# S7_IO.net
KiCad netlist of a schematic drawn in Altium Designer
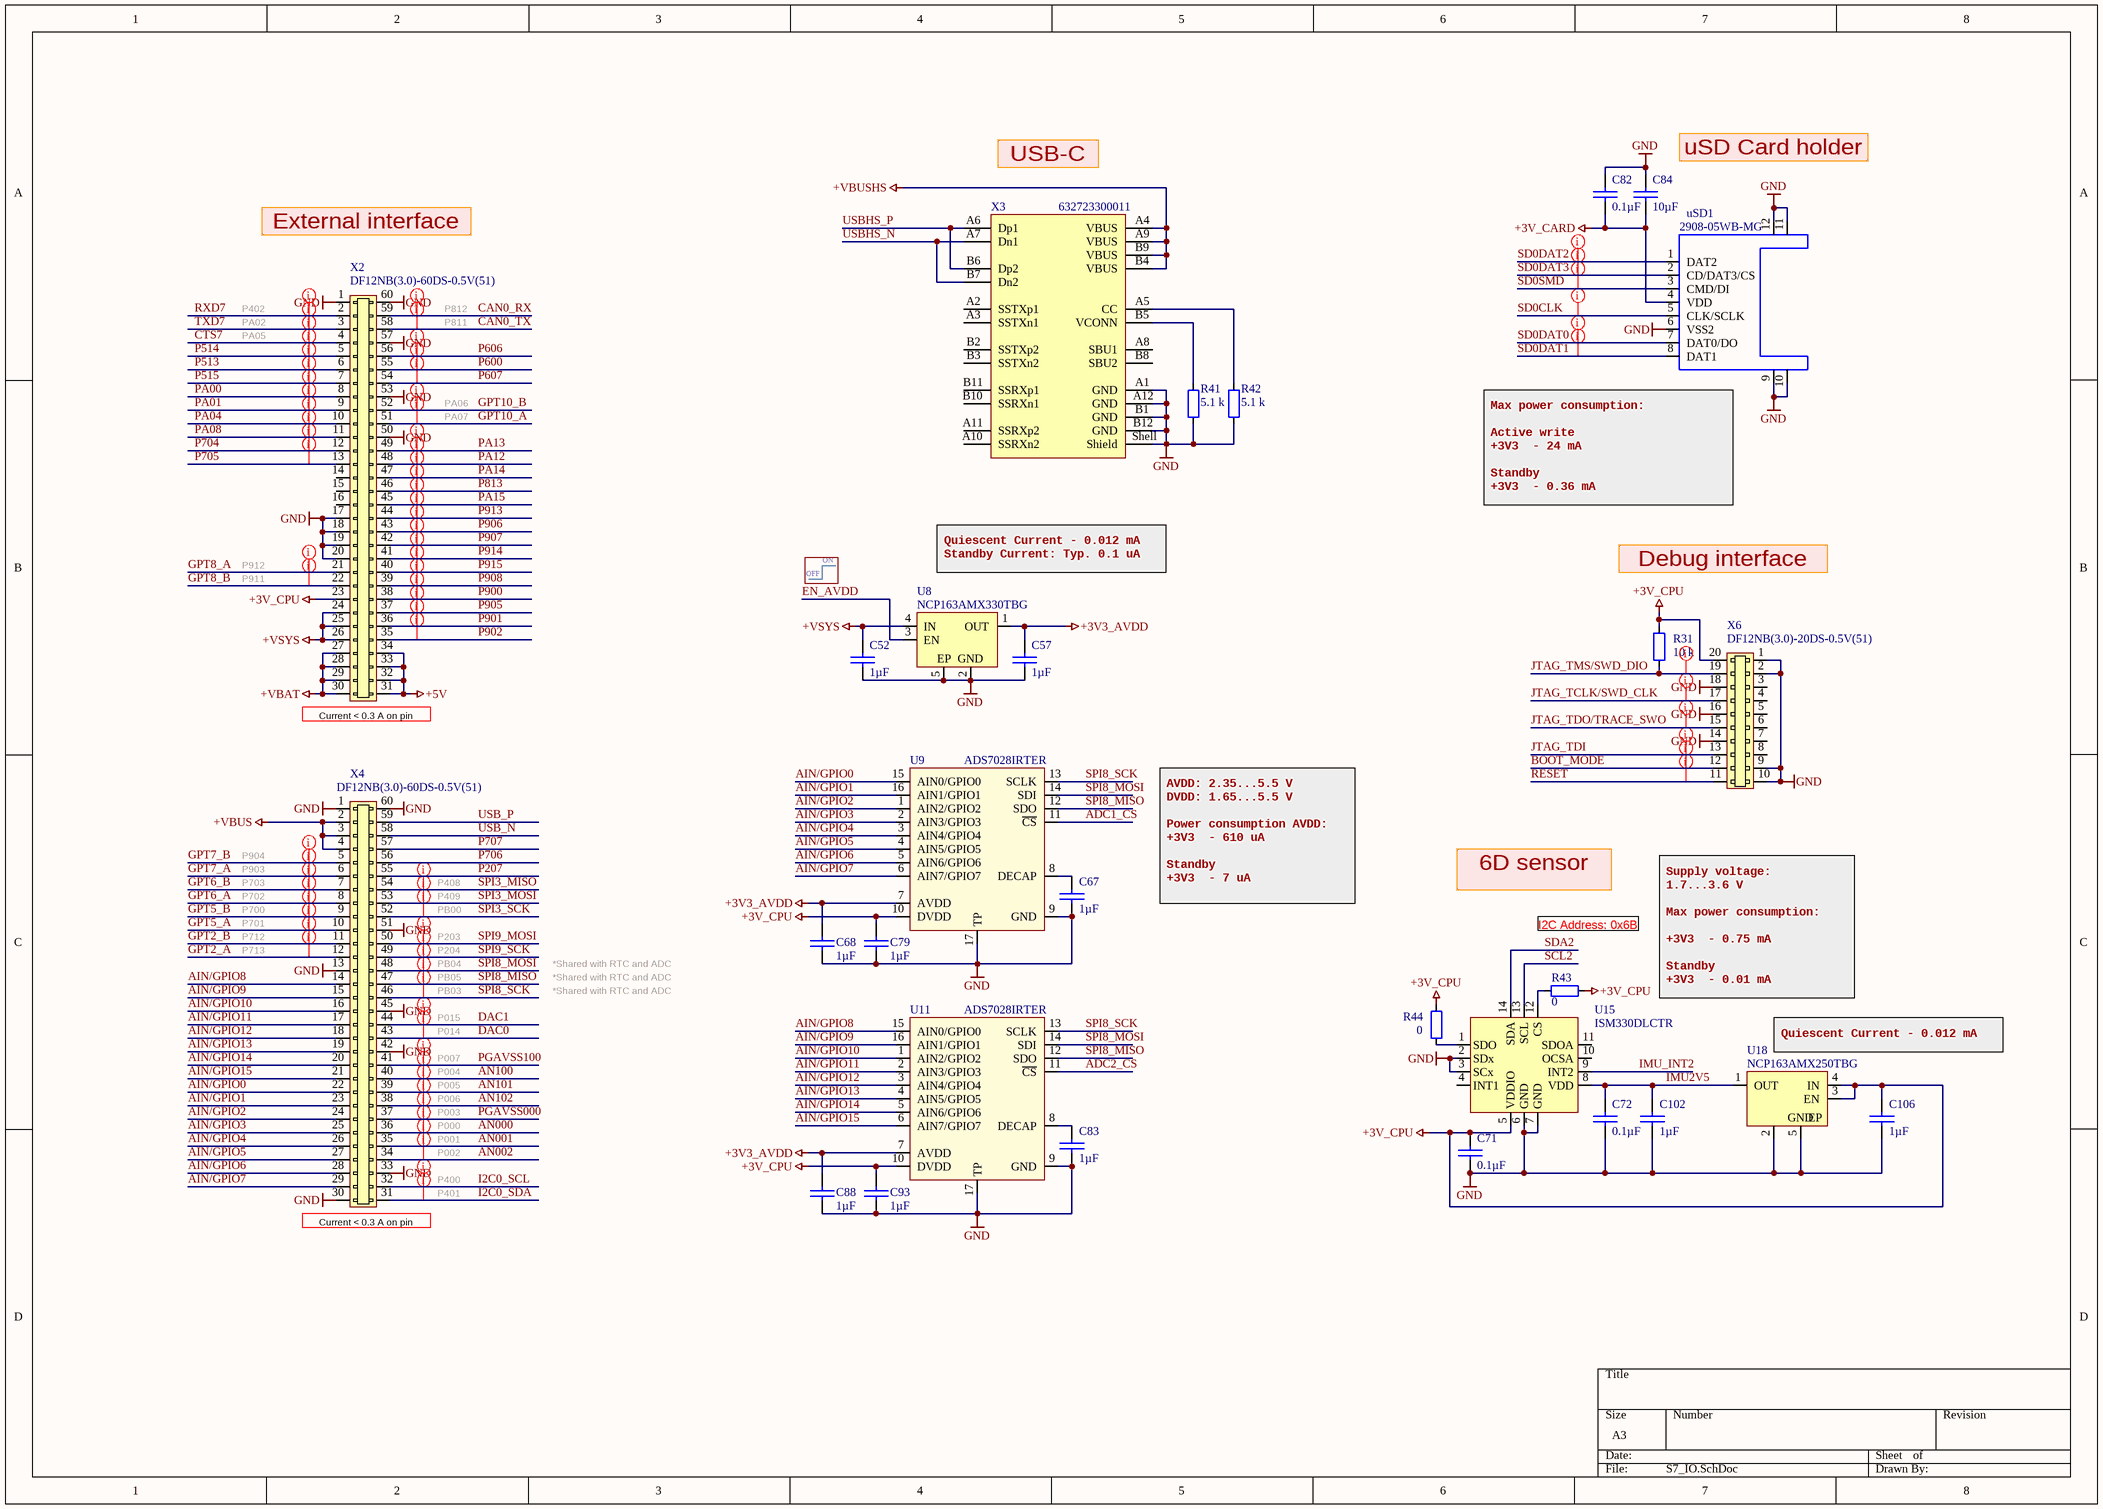
[diagram p0: S7_IO.SchDoc]

(export (version "E")
  (design (tool "Eeschema 10.0.6"))
  (components
    (comp (ref "C52")
      (value "1µF")
      (footprint "0402 CAP")
      (description "1µF, ±20%, 25V, X5R, 0402 (1005 Metric), -55°C ~ 85°C, -, General Purpose")
      (fields (field (name "PART NUMBER") "TMK105BJ105MV-F") (field (name "MANUFACTURER") "Taiyo Yuden"))
      (libsource (lib "ea_PassivComps") (part "Capacitor"))
    )
    (comp (ref "C57")
      (value "1µF")
      (footprint "0402 CAP")
      (description "1µF, ±20%, 25V, X5R, 0402 (1005 Metric), -55°C ~ 85°C, -, General Purpose")
      (fields (field (name "PART NUMBER") "TMK105BJ105MV-F") (field (name "MANUFACTURER") "Taiyo Yuden"))
      (libsource (lib "ea_PassivComps") (part "Capacitor"))
    )
    (comp (ref "C67")
      (value "1µF")
      (footprint "0402 CAP")
      (description "1µF, ±20%, 25V, X5R, 0402 (1005 Metric), -55°C ~ 85°C, -, General Purpose")
      (fields (field (name "PART NUMBER") "TMK105BJ105MV-F") (field (name "MANUFACTURER") "Taiyo Yuden"))
      (libsource (lib "ea_PassivComps") (part "Capacitor"))
    )
    (comp (ref "C68")
      (value "1µF")
      (footprint "0402 CAP")
      (description "1µF, ±20%, 25V, X5R, 0402 (1005 Metric), -55°C ~ 85°C, -, General Purpose")
      (fields (field (name "PART NUMBER") "TMK105BJ105MV-F") (field (name "MANUFACTURER") "Taiyo Yuden"))
      (libsource (lib "ea_PassivComps") (part "Capacitor"))
    )
    (comp (ref "C71")
      (value "0.1µF")
      (footprint "0402 CAP")
      (description "0.1µF, ±10%, 50V, X7R, 0402 (1005 Metric), -55°C ~ 125°C, -, General Purpose")
      (fields
        (field (name "PART NUMBER") "0402B104K500CT")
        (field (name "MANUFACTURER") "Walsin Technology Corporation")
      )
      (libsource (lib "ea_PassivComps") (part "Capacitor"))
    )
    (comp (ref "C72")
      (value "0.1µF")
      (footprint "0402 CAP")
      (description "0.1µF, ±10%, 50V, X7R, 0402 (1005 Metric), -55°C ~ 125°C, -, General Purpose")
      (fields
        (field (name "PART NUMBER") "0402B104K500CT")
        (field (name "MANUFACTURER") "Walsin Technology Corporation")
      )
      (libsource (lib "ea_PassivComps") (part "Capacitor"))
    )
    (comp (ref "C79")
      (value "1µF")
      (footprint "0402 CAP")
      (description "1µF, ±20%, 25V, X5R, 0402 (1005 Metric), -55°C ~ 85°C, -, General Purpose")
      (fields (field (name "PART NUMBER") "TMK105BJ105MV-F") (field (name "MANUFACTURER") "Taiyo Yuden"))
      (libsource (lib "ea_PassivComps") (part "Capacitor"))
    )
    (comp (ref "C82")
      (value "0.1µF")
      (footprint "0402 CAP")
      (description "0.1µF, ±10%, 50V, X7R, 0402 (1005 Metric), -55°C ~ 125°C, -, General Purpose")
      (fields
        (field (name "PART NUMBER") "0402B104K500CT")
        (field (name "MANUFACTURER") "Walsin Technology Corporation")
      )
      (libsource (lib "ea_PassivComps") (part "Capacitor"))
    )
    (comp (ref "C83")
      (value "1µF")
      (footprint "0402 CAP")
      (description "1µF, ±20%, 25V, X5R, 0402 (1005 Metric), -55°C ~ 85°C, -, General Purpose")
      (fields (field (name "PART NUMBER") "TMK105BJ105MV-F") (field (name "MANUFACTURER") "Taiyo Yuden"))
      (libsource (lib "ea_PassivComps") (part "Capacitor"))
    )
    (comp (ref "C84")
      (value "10µF")
      (footprint "0603 CAP")
      (description "10µF, ±10%, 16V, X5R, 0603 (1608 Metric), -55°C ~ 85°C, -, Automotive")
      (fields
        (field (name "PART NUMBER") "GRT188R61C106KE13D")
        (field (name "MANUFACTURER") "Murata Electronics North America")
      )
      (libsource (lib "ea_PassivComps") (part "Capacitor"))
    )
    (comp (ref "C88")
      (value "1µF")
      (footprint "0402 CAP")
      (description "1µF, ±20%, 25V, X5R, 0402 (1005 Metric), -55°C ~ 85°C, -, General Purpose")
      (fields (field (name "PART NUMBER") "TMK105BJ105MV-F") (field (name "MANUFACTURER") "Taiyo Yuden"))
      (libsource (lib "ea_PassivComps") (part "Capacitor"))
    )
    (comp (ref "C93")
      (value "1µF")
      (footprint "0402 CAP")
      (description "1µF, ±20%, 25V, X5R, 0402 (1005 Metric), -55°C ~ 85°C, -, General Purpose")
      (fields (field (name "PART NUMBER") "TMK105BJ105MV-F") (field (name "MANUFACTURER") "Taiyo Yuden"))
      (libsource (lib "ea_PassivComps") (part "Capacitor"))
    )
    (comp (ref "C102")
      (value "1µF")
      (footprint "0402 CAP")
      (description "1µF, ±20%, 25V, X5R, 0402 (1005 Metric), -55°C ~ 85°C, -, General Purpose")
      (fields (field (name "PART NUMBER") "TMK105BJ105MV-F") (field (name "MANUFACTURER") "Taiyo Yuden"))
      (libsource (lib "ea_PassivComps") (part "Capacitor"))
    )
    (comp (ref "C106")
      (value "1µF")
      (footprint "0402 CAP")
      (description "1µF, ±20%, 25V, X5R, 0402 (1005 Metric), -55°C ~ 85°C, -, General Purpose")
      (fields (field (name "PART NUMBER") "TMK105BJ105MV-F") (field (name "MANUFACTURER") "Taiyo Yuden"))
      (libsource (lib "ea_PassivComps") (part "Capacitor"))
    )
    (comp (ref "R31")
      (value "10 k")
      (footprint "0402")
      (fields
        (field (name "MANUFACTURER") "Stackpole Electronics Inc")
        (field (name "TOLERANCE") "±1%")
        (field (name "PARTNUM") "RMCF0402FT10K0CT-ND")
      )
      (libsource (lib "ea_PassivComps") (part "Resistor"))
    )
    (comp (ref "R41")
      (value "5.1 k")
      (footprint "0402")
      (fields
        (field (name "MANUFACTURER") "Stackpole Electronics Inc")
        (field (name "TOLERANCE") "±1%")
        (field (name "VOLTAGE") "75V")
      )
      (libsource (lib "ea_PassivComps") (part "Resistor"))
    )
    (comp (ref "R42")
      (value "5.1 k")
      (footprint "0402")
      (fields
        (field (name "MANUFACTURER") "Stackpole Electronics Inc")
        (field (name "TOLERANCE") "±1%")
        (field (name "VOLTAGE") "75V")
      )
      (libsource (lib "ea_PassivComps") (part "Resistor"))
    )
    (comp (ref "R43")
      (value "0")
      (footprint "0402")
      (description "0 Ohms Jumper 0.063W, 1/16W Chip Resistor 0402 (1005 Metric) Thick Film")
      (fields (field (name "MANUFACTURER") "Walsin Technology Corporation") (field (name "VOLTAGE") "50 V"))
      (libsource (lib "") (part "WR04X000 PTL_1"))
    )
    (comp (ref "R44")
      (value "0")
      (footprint "0402")
      (description "0 Ohms Jumper 0.063W, 1/16W Chip Resistor 0402 (1005 Metric) Thick Film")
      (fields (field (name "MANUFACTURER") "Walsin Technology Corporation") (field (name "VOLTAGE") "50 V"))
      (libsource (lib "ea_Resistors_0402") (part "WR04X000 PTL"))
    )
    (comp (ref "U8")
      (value "NCP163AMX330TBG")
      (footprint "4-XDFN")
      (description "LDO 3.3V, 250 mA, Vin < 5.5V, Iq < 20uA, -40..+125 C,  4-XDFN (1x1)")
      (fields
        (field (name "MANUFACTURER") "ON Semiconductor")
        (field (name "PARTNUM") "NCP163AMX330TBGOSCT-ND")
      )
      (libsource (lib "ea_IC_Linear_reg_LDO") (part "NCP163AMX330TBG"))
    )
    (comp (ref "U9")
      (value "ADS7028IRTER")
      (footprint "WQFN-16 3x3mm TI")
      (description "12 Bit Analog to Digital Converter 8 Input 1 SAR, 2.35V ~ 5.5V, 16-WQFN (3x3),  -40°C ~ 85°C")
      (fields
        (field (name "MANUFACTURER") "Texas Instruments")
        (field (name "PARTNUM") "296-ADS7028IRTERCT-ND")
      )
      (libsource (lib "ea_IC_ADC") (part "ADS7028IRTER"))
    )
    (comp (ref "U11")
      (value "ADS7028IRTER")
      (footprint "WQFN-16 3x3mm TI")
      (description "12 Bit Analog to Digital Converter 8 Input 1 SAR, 2.35V ~ 5.5V, 16-WQFN (3x3),  -40°C ~ 85°C")
      (fields
        (field (name "MANUFACTURER") "Texas Instruments")
        (field (name "PARTNUM") "296-ADS7028IRTERCT-ND")
      )
      (libsource (lib "ea_IC_ADC") (part "ADS7028IRTER"))
    )
    (comp (ref "U15")
      (value "ISM330DLCTR")
      (footprint "LGA-14 BOSCH")
      (description "Accelerometer, Gyroscope, Temperature, 3 Axis Sensor I²C, SPI , -40°C ~ 85°C, 14-LGA (2.5x3)")
      (fields (field (name "MANUFACTURER") "STMicroelectronics") (field (name "PARTNUM") "497-17583-1-ND"))
      (libsource (lib "ea_IC_sensors") (part "ISM330DLCTR"))
    )
    (comp (ref "U18")
      (value "NCP163AMX250TBG")
      (footprint "4-XDFN")
      (description "LDO 2.5V, 250 mA, Vin < 5.5V, Iq < 20uA, -40..+125 C,  4-XDFN (1x1)")
      (fields
        (field (name "MANUFACTURER") "ON Semiconductor")
        (field (name "PARTNUM") "NCP163AMX250TBGOSCT-ND")
      )
      (libsource (lib "ea_IC_Power_Reg_Ref_Sw") (part "NCP163AMX250TBG"))
    )
    (comp (ref "uSD1")
      (value "2908-05WB-MG")
      (footprint "2908-05WB-MG")
      (description "microSD cadr holder")
      (fields (field (name "MANUFACTURER") "3M"))
      (libsource (lib "ea_CARD_holders") (part "2908-05WB-MG"))
    )
    (comp (ref "X2")
      (value "DF12NB(3.0)-60DS-0.5V(51)")
      (footprint "DF12NB(3.0)-60DS-0.5V(51)")
      (fields
        (field (name "MANUFACTURER") "Hirose Electric")
        (field (name "PARTNUM") "26-DF12NB(3.0)-60DS-0.5V(51)CT-ND")
      )
      (libsource (lib "ea_Connectors_0.5_mm_pitch") (part "DF12NB(3.0)-60DS-0.5V(51)"))
    )
    (comp (ref "X3")
      (value "632723300011")
      (footprint "632723300011")
      (description "WR-USB 3.1 Type C, Receptacle, Horizontal, THR")
      (fields (field (name "MANUFACTURER") "Wurth Elektronik"))
      (libsource (lib "WR-USB") (part "632723300011"))
    )
    (comp (ref "X4")
      (value "DF12NB(3.0)-60DS-0.5V(51)")
      (footprint "DF12NB(3.0)-60DS-0.5V(51)")
      (fields
        (field (name "MANUFACTURER") "Hirose Electric")
        (field (name "PARTNUM") "26-DF12NB(3.0)-60DS-0.5V(51)CT-ND")
      )
      (libsource (lib "ea_Connectors_0.5_mm_pitch") (part "DF12NB(3.0)-60DS-0.5V(51)"))
    )
    (comp (ref "X6")
      (value "DF12NB(3.0)-20DS-0.5V(51)")
      (footprint "DF12NB(3.0)-20DS-0.5V(51)")
      (fields
        (field (name "MANUFACTURER") "Hirose Electric")
        (field (name "PARTNUM") "26-DF12NB(3.0)-20DS-0.5V(51)CT-ND - Cut Tape (CT)")
      )
      (libsource (lib "ea_Connectors_0.5_mm_pitch") (part "DF12NB(3.0)-20DS-0.5V(51)"))
    )
  )
  (nets
    (net (code "1") (name "+3V3_AVDD") (class "Default")
      (node (ref "C57") (pin "1") (pinfunction "1_1") (pintype "passive"))
      (node (ref "C68") (pin "1") (pinfunction "1_1") (pintype "passive"))
      (node (ref "C88") (pin "1") (pinfunction "1_1") (pintype "passive"))
      (node (ref "U11") (pin "7") (pinfunction "AVDD_7") (pintype "passive"))
      (node (ref "U8") (pin "1") (pinfunction "OUT_1") (pintype "power_in"))
      (node (ref "U9") (pin "7") (pinfunction "AVDD_7") (pintype "passive"))
    )
    (net (code "2") (name "+3V_CARD") (class "Default")
      (node (ref "C82") (pin "2") (pinfunction "2_2") (pintype "passive"))
      (node (ref "C84") (pin "2") (pinfunction "2_2") (pintype "passive"))
      (node (ref "uSD1") (pin "4") (pinfunction "VDD_4") (pintype "passive"))
    )
    (net (code "3") (name "+3V_CPU") (class "Default")
      (node (ref "C106") (pin "1") (pinfunction "1_1") (pintype "passive"))
      (node (ref "C71") (pin "1") (pinfunction "1_1") (pintype "passive"))
      (node (ref "C79") (pin "1") (pinfunction "1_1") (pintype "passive"))
      (node (ref "C93") (pin "1") (pinfunction "1_1") (pintype "passive"))
      (node (ref "R31") (pin "2") (pinfunction "2_2") (pintype "passive"))
      (node (ref "R43") (pin "1") (pinfunction "1_1") (pintype "passive"))
      (node (ref "R44") (pin "2") (pinfunction "2_2") (pintype "passive"))
      (node (ref "U11") (pin "10") (pinfunction "DVDD_10") (pintype "passive"))
      (node (ref "U15") (pin "5") (pinfunction "VDDIO_5") (pintype "passive"))
      (node (ref "U18") (pin "3") (pinfunction "EN_3") (pintype "power_in"))
      (node (ref "U18") (pin "4") (pinfunction "IN_4") (pintype "power_in"))
      (node (ref "U9") (pin "10") (pinfunction "DVDD_10") (pintype "passive"))
      (node (ref "X2") (pin "23") (pinfunction "23_23") (pintype "passive"))
      (node (ref "X6") (pin "20") (pinfunction "11_20") (pintype "passive"))
    )
    (net (code "4") (name "+5V") (class "Default")
      (node (ref "X2") (pin "31") (pinfunction "31_31") (pintype "passive"))
      (node (ref "X2") (pin "32") (pinfunction "32_32") (pintype "passive"))
      (node (ref "X2") (pin "33") (pinfunction "33_33") (pintype "passive"))
      (node (ref "X2") (pin "34") (pinfunction "34_34") (pintype "passive"))
    )
    (net (code "5") (name "+VBAT") (class "Default")
      (node (ref "X2") (pin "27") (pinfunction "27_27") (pintype "passive"))
      (node (ref "X2") (pin "28") (pinfunction "28_28") (pintype "passive"))
      (node (ref "X2") (pin "29") (pinfunction "29_29") (pintype "passive"))
      (node (ref "X2") (pin "30") (pinfunction "30_30") (pintype "passive"))
    )
    (net (code "6") (name "+VBUS") (class "Default")
      (node (ref "X4") (pin "2") (pinfunction "2_2") (pintype "passive"))
      (node (ref "X4") (pin "3") (pinfunction "3_3") (pintype "passive"))
      (node (ref "X4") (pin "4") (pinfunction "4_4") (pintype "passive"))
    )
    (net (code "7") (name "+VBUSHS") (class "Default")
      (node (ref "X3") (pin "A4") (pinfunction "VBUS_A4") (pintype "passive"))
      (node (ref "X3") (pin "A9") (pinfunction "VBUS_A9") (pintype "passive"))
      (node (ref "X3") (pin "B4") (pinfunction "VBUS_B4") (pintype "passive"))
      (node (ref "X3") (pin "B9") (pinfunction "VBUS_B9") (pintype "passive"))
    )
    (net (code "8") (name "+VSYS") (class "Default")
      (node (ref "C52") (pin "1") (pinfunction "1_1") (pintype "passive"))
      (node (ref "U8") (pin "4") (pinfunction "IN_4") (pintype "power_in"))
      (node (ref "X2") (pin "24") (pinfunction "24_24") (pintype "passive"))
      (node (ref "X2") (pin "25") (pinfunction "25_25") (pintype "passive"))
      (node (ref "X2") (pin "26") (pinfunction "26_26") (pintype "passive"))
    )
    (net (code "9") (name "/ADC1_CS") (class "Default")
      (node (ref "U9") (pin "11") (pinfunction "~{CS}_11") (pintype "passive"))
    )
    (net (code "10") (name "/ADC2_CS") (class "Default")
      (node (ref "U11") (pin "11") (pinfunction "~{CS}_11") (pintype "passive"))
    )
    (net (code "11") (name "/AIN{slash}GPIO0") (class "Default")
      (node (ref "U9") (pin "15") (pinfunction "AIN0/GPIO0_15") (pintype "passive"))
      (node (ref "X4") (pin "22") (pinfunction "22_22") (pintype "passive"))
    )
    (net (code "12") (name "/AIN{slash}GPIO1") (class "Default")
      (node (ref "U9") (pin "16") (pinfunction "AIN1/GPIO1_16") (pintype "passive"))
      (node (ref "X4") (pin "23") (pinfunction "23_23") (pintype "passive"))
    )
    (net (code "13") (name "/AIN{slash}GPIO2") (class "Default")
      (node (ref "U9") (pin "1") (pinfunction "AIN2/GPIO2_1") (pintype "passive"))
      (node (ref "X4") (pin "24") (pinfunction "24_24") (pintype "passive"))
    )
    (net (code "14") (name "/AIN{slash}GPIO3") (class "Default")
      (node (ref "U9") (pin "2") (pinfunction "AIN3/GPIO3_2") (pintype "passive"))
      (node (ref "X4") (pin "25") (pinfunction "25_25") (pintype "passive"))
    )
    (net (code "15") (name "/AIN{slash}GPIO4") (class "Default")
      (node (ref "U9") (pin "3") (pinfunction "AIN4/GPIO4_3") (pintype "passive"))
      (node (ref "X4") (pin "26") (pinfunction "26_26") (pintype "passive"))
    )
    (net (code "16") (name "/AIN{slash}GPIO5") (class "Default")
      (node (ref "U9") (pin "4") (pinfunction "AIN5/GPIO5_4") (pintype "passive"))
      (node (ref "X4") (pin "27") (pinfunction "27_27") (pintype "passive"))
    )
    (net (code "17") (name "/AIN{slash}GPIO6") (class "Default")
      (node (ref "U9") (pin "5") (pinfunction "AIN6/GPIO6_5") (pintype "passive"))
      (node (ref "X4") (pin "28") (pinfunction "28_28") (pintype "passive"))
    )
    (net (code "18") (name "/AIN{slash}GPIO7") (class "Default")
      (node (ref "U9") (pin "6") (pinfunction "AIN7/GPIO7_6") (pintype "passive"))
      (node (ref "X4") (pin "29") (pinfunction "29_29") (pintype "passive"))
    )
    (net (code "19") (name "/AIN{slash}GPIO8") (class "Default")
      (node (ref "U11") (pin "15") (pinfunction "AIN0/GPIO0_15") (pintype "passive"))
      (node (ref "X4") (pin "14") (pinfunction "14_14") (pintype "passive"))
    )
    (net (code "20") (name "/AIN{slash}GPIO9") (class "Default")
      (node (ref "U11") (pin "16") (pinfunction "AIN1/GPIO1_16") (pintype "passive"))
      (node (ref "X4") (pin "15") (pinfunction "15_15") (pintype "passive"))
    )
    (net (code "21") (name "/AIN{slash}GPIO10") (class "Default")
      (node (ref "U11") (pin "1") (pinfunction "AIN2/GPIO2_1") (pintype "passive"))
      (node (ref "X4") (pin "16") (pinfunction "16_16") (pintype "passive"))
    )
    (net (code "22") (name "/AIN{slash}GPIO11") (class "Default")
      (node (ref "U11") (pin "2") (pinfunction "AIN3/GPIO3_2") (pintype "passive"))
      (node (ref "X4") (pin "17") (pinfunction "17_17") (pintype "passive"))
    )
    (net (code "23") (name "/AIN{slash}GPIO12") (class "Default")
      (node (ref "U11") (pin "3") (pinfunction "AIN4/GPIO4_3") (pintype "passive"))
      (node (ref "X4") (pin "18") (pinfunction "18_18") (pintype "passive"))
    )
    (net (code "24") (name "/AIN{slash}GPIO13") (class "Default")
      (node (ref "U11") (pin "4") (pinfunction "AIN5/GPIO5_4") (pintype "passive"))
      (node (ref "X4") (pin "19") (pinfunction "19_19") (pintype "passive"))
    )
    (net (code "25") (name "/AIN{slash}GPIO14") (class "Default")
      (node (ref "U11") (pin "5") (pinfunction "AIN6/GPIO6_5") (pintype "passive"))
      (node (ref "X4") (pin "20") (pinfunction "20_20") (pintype "passive"))
    )
    (net (code "26") (name "/AIN{slash}GPIO15") (class "Default")
      (node (ref "U11") (pin "6") (pinfunction "AIN7/GPIO7_6") (pintype "passive"))
      (node (ref "X4") (pin "21") (pinfunction "21_21") (pintype "passive"))
    )
    (net (code "27") (name "/AN000") (class "Default")
      (node (ref "X4") (pin "36") (pinfunction "36_36") (pintype "passive"))
    )
    (net (code "28") (name "/AN001") (class "Default")
      (node (ref "X4") (pin "35") (pinfunction "35_35") (pintype "passive"))
    )
    (net (code "29") (name "/AN002") (class "Default")
      (node (ref "X4") (pin "34") (pinfunction "34_34") (pintype "passive"))
    )
    (net (code "30") (name "/AN100") (class "Default")
      (node (ref "X4") (pin "40") (pinfunction "40_40") (pintype "passive"))
    )
    (net (code "31") (name "/AN101") (class "Default")
      (node (ref "X4") (pin "39") (pinfunction "39_39") (pintype "passive"))
    )
    (net (code "32") (name "/AN102") (class "Default")
      (node (ref "X4") (pin "38") (pinfunction "38_38") (pintype "passive"))
    )
    (net (code "33") (name "/BOOT_MODE") (class "Default")
      (node (ref "X6") (pin "12") (pinfunction "7_12") (pintype "passive"))
    )
    (net (code "34") (name "/CAN0_RX") (class "Default")
      (node (ref "X2") (pin "59") (pinfunction "59_59") (pintype "passive"))
    )
    (net (code "35") (name "/CAN0_TX") (class "Default")
      (node (ref "X2") (pin "58") (pinfunction "58_58") (pintype "passive"))
    )
    (net (code "36") (name "/CTS7") (class "Default")
      (node (ref "X2") (pin "4") (pinfunction "4_4") (pintype "passive"))
    )
    (net (code "37") (name "/DAC0") (class "Default")
      (node (ref "X4") (pin "43") (pinfunction "43_43") (pintype "passive"))
    )
    (net (code "38") (name "/DAC1") (class "Default")
      (node (ref "X4") (pin "44") (pinfunction "44_44") (pintype "passive"))
    )
    (net (code "39") (name "/EN_AVDD") (class "Default")
      (node (ref "U8") (pin "3") (pinfunction "EN_3") (pintype "power_in"))
    )
    (net (code "40") (name "/GPT2_A") (class "Default")
      (node (ref "X4") (pin "12") (pinfunction "12_12") (pintype "passive"))
    )
    (net (code "41") (name "/GPT2_B") (class "Default")
      (node (ref "X4") (pin "11") (pinfunction "11_11") (pintype "passive"))
    )
    (net (code "42") (name "/GPT5_A") (class "Default")
      (node (ref "X4") (pin "10") (pinfunction "10_10") (pintype "passive"))
    )
    (net (code "43") (name "/GPT5_B") (class "Default")
      (node (ref "X4") (pin "9") (pinfunction "9_9") (pintype "passive"))
    )
    (net (code "44") (name "/GPT6_A") (class "Default")
      (node (ref "X4") (pin "8") (pinfunction "8_8") (pintype "passive"))
    )
    (net (code "45") (name "/GPT6_B") (class "Default")
      (node (ref "X4") (pin "7") (pinfunction "7_7") (pintype "passive"))
    )
    (net (code "46") (name "/GPT7_A") (class "Default")
      (node (ref "X4") (pin "6") (pinfunction "6_6") (pintype "passive"))
    )
    (net (code "47") (name "/GPT7_B") (class "Default")
      (node (ref "X4") (pin "5") (pinfunction "5_5") (pintype "passive"))
    )
    (net (code "48") (name "/GPT8_A") (class "Default")
      (node (ref "X2") (pin "21") (pinfunction "21_21") (pintype "passive"))
    )
    (net (code "49") (name "/GPT8_B") (class "Default")
      (node (ref "X2") (pin "22") (pinfunction "22_22") (pintype "passive"))
    )
    (net (code "50") (name "/GPT10_A") (class "Default")
      (node (ref "X2") (pin "51") (pinfunction "51_51") (pintype "passive"))
    )
    (net (code "51") (name "/GPT10_B") (class "Default")
      (node (ref "X2") (pin "52") (pinfunction "52_52") (pintype "passive"))
    )
    (net (code "52") (name "/I2C0_SCL") (class "Default")
      (node (ref "X4") (pin "32") (pinfunction "32_32") (pintype "passive"))
    )
    (net (code "53") (name "/I2C0_SDA") (class "Default")
      (node (ref "X4") (pin "31") (pinfunction "31_31") (pintype "passive"))
    )
    (net (code "54") (name "/IMU2V5") (class "Default")
      (node (ref "C102") (pin "1") (pinfunction "1_1") (pintype "passive"))
      (node (ref "C72") (pin "1") (pinfunction "1_1") (pintype "passive"))
      (node (ref "U15") (pin "8") (pinfunction "VDD_8") (pintype "passive"))
      (node (ref "U18") (pin "1") (pinfunction "OUT_1") (pintype "power_in"))
    )
    (net (code "55") (name "/IMU_INT2") (class "Default")
      (node (ref "U15") (pin "9") (pinfunction "INT2_9") (pintype "passive"))
    )
    (net (code "56") (name "/JTAG_TCLK{slash}SWD_CLK") (class "Default")
      (node (ref "X6") (pin "17") (pinfunction "9_17") (pintype "passive"))
    )
    (net (code "57") (name "/JTAG_TDI") (class "Default")
      (node (ref "X6") (pin "13") (pinfunction "7_13") (pintype "passive"))
    )
    (net (code "58") (name "/JTAG_TDO{slash}TRACE_SWO") (class "Default")
      (node (ref "X6") (pin "15") (pinfunction "8_15") (pintype "passive"))
    )
    (net (code "59") (name "/JTAG_TMS{slash}SWD_DIO") (class "Default")
      (node (ref "R31") (pin "1") (pinfunction "1_1") (pintype "passive"))
      (node (ref "X6") (pin "19") (pinfunction "10_19") (pintype "passive"))
    )
    (net (code "60") (name "/P207") (class "Default")
      (node (ref "X4") (pin "55") (pinfunction "55_55") (pintype "passive"))
    )
    (net (code "61") (name "/P513") (class "Default")
      (node (ref "X2") (pin "6") (pinfunction "6_6") (pintype "passive"))
    )
    (net (code "62") (name "/P514") (class "Default")
      (node (ref "X2") (pin "5") (pinfunction "5_5") (pintype "passive"))
    )
    (net (code "63") (name "/P515") (class "Default")
      (node (ref "X2") (pin "7") (pinfunction "7_7") (pintype "passive"))
    )
    (net (code "64") (name "/P600") (class "Default")
      (node (ref "X2") (pin "55") (pinfunction "55_55") (pintype "passive"))
    )
    (net (code "65") (name "/P606") (class "Default")
      (node (ref "X2") (pin "56") (pinfunction "56_56") (pintype "passive"))
    )
    (net (code "66") (name "/P607") (class "Default")
      (node (ref "X2") (pin "54") (pinfunction "54_54") (pintype "passive"))
    )
    (net (code "67") (name "/P704") (class "Default")
      (node (ref "X2") (pin "12") (pinfunction "12_12") (pintype "passive"))
    )
    (net (code "68") (name "/P705") (class "Default")
      (node (ref "X2") (pin "13") (pinfunction "13_13") (pintype "passive"))
    )
    (net (code "69") (name "/P706") (class "Default")
      (node (ref "X4") (pin "56") (pinfunction "56_56") (pintype "passive"))
    )
    (net (code "70") (name "/P707") (class "Default")
      (node (ref "X4") (pin "57") (pinfunction "57_57") (pintype "passive"))
    )
    (net (code "71") (name "/P813") (class "Default")
      (node (ref "X2") (pin "46") (pinfunction "46_46") (pintype "passive"))
    )
    (net (code "72") (name "/P900") (class "Default")
      (node (ref "X2") (pin "38") (pinfunction "38_38") (pintype "passive"))
    )
    (net (code "73") (name "/P901") (class "Default")
      (node (ref "X2") (pin "36") (pinfunction "36_36") (pintype "passive"))
    )
    (net (code "74") (name "/P902") (class "Default")
      (node (ref "X2") (pin "35") (pinfunction "35_35") (pintype "passive"))
    )
    (net (code "75") (name "/P905") (class "Default")
      (node (ref "X2") (pin "37") (pinfunction "37_37") (pintype "passive"))
    )
    (net (code "76") (name "/P906") (class "Default")
      (node (ref "X2") (pin "43") (pinfunction "43_43") (pintype "passive"))
    )
    (net (code "77") (name "/P907") (class "Default")
      (node (ref "X2") (pin "42") (pinfunction "42_42") (pintype "passive"))
    )
    (net (code "78") (name "/P908") (class "Default")
      (node (ref "X2") (pin "39") (pinfunction "39_39") (pintype "passive"))
    )
    (net (code "79") (name "/P913") (class "Default")
      (node (ref "X2") (pin "44") (pinfunction "44_44") (pintype "passive"))
    )
    (net (code "80") (name "/P914") (class "Default")
      (node (ref "X2") (pin "41") (pinfunction "41_41") (pintype "passive"))
    )
    (net (code "81") (name "/P915") (class "Default")
      (node (ref "X2") (pin "40") (pinfunction "40_40") (pintype "passive"))
    )
    (net (code "82") (name "/PA00") (class "Default")
      (node (ref "X2") (pin "8") (pinfunction "8_8") (pintype "passive"))
    )
    (net (code "83") (name "/PA01") (class "Default")
      (node (ref "X2") (pin "9") (pinfunction "9_9") (pintype "passive"))
    )
    (net (code "84") (name "/PA04") (class "Default")
      (node (ref "X2") (pin "10") (pinfunction "10_10") (pintype "passive"))
    )
    (net (code "85") (name "/PA08") (class "Default")
      (node (ref "X2") (pin "11") (pinfunction "11_11") (pintype "passive"))
    )
    (net (code "86") (name "/PA12") (class "Default")
      (node (ref "X2") (pin "48") (pinfunction "48_48") (pintype "passive"))
    )
    (net (code "87") (name "/PA13") (class "Default")
      (node (ref "X2") (pin "49") (pinfunction "49_49") (pintype "passive"))
    )
    (net (code "88") (name "/PA14") (class "Default")
      (node (ref "X2") (pin "47") (pinfunction "47_47") (pintype "passive"))
    )
    (net (code "89") (name "/PA15") (class "Default")
      (node (ref "X2") (pin "45") (pinfunction "45_45") (pintype "passive"))
    )
    (net (code "90") (name "/PGAVSS000") (class "Default")
      (node (ref "X4") (pin "37") (pinfunction "37_37") (pintype "passive"))
    )
    (net (code "91") (name "/PGAVSS100") (class "Default")
      (node (ref "X4") (pin "41") (pinfunction "41_41") (pintype "passive"))
    )
    (net (code "92") (name "/RESET") (class "Default")
      (node (ref "X6") (pin "11") (pinfunction "6_11") (pintype "passive"))
    )
    (net (code "93") (name "/RXD7") (class "Default")
      (node (ref "X2") (pin "2") (pinfunction "2_2") (pintype "passive"))
    )
    (net (code "94") (name "/SCL2") (class "Default")
      (node (ref "U15") (pin "13") (pinfunction "SCL_13") (pintype "passive"))
    )
    (net (code "95") (name "/SD0CLK") (class "Default")
      (node (ref "uSD1") (pin "5") (pinfunction "CLK/SCLK_5") (pintype "passive"))
    )
    (net (code "96") (name "/SD0DAT0") (class "Default")
      (node (ref "uSD1") (pin "7") (pinfunction "DAT0/DO_7") (pintype "passive"))
    )
    (net (code "97") (name "/SD0DAT1") (class "Default")
      (node (ref "uSD1") (pin "8") (pinfunction "DAT1_8") (pintype "passive"))
    )
    (net (code "98") (name "/SD0DAT2") (class "Default")
      (node (ref "uSD1") (pin "1") (pinfunction "DAT2_1") (pintype "passive"))
    )
    (net (code "99") (name "/SD0DAT3") (class "Default")
      (node (ref "uSD1") (pin "2") (pinfunction "CD/DAT3/CS_2") (pintype "passive"))
    )
    (net (code "100") (name "/SD0SMD") (class "Default")
      (node (ref "uSD1") (pin "3") (pinfunction "CMD/DI_3") (pintype "passive"))
    )
    (net (code "101") (name "/SDA2") (class "Default")
      (node (ref "U15") (pin "14") (pinfunction "SDA_14") (pintype "passive"))
    )
    (net (code "102") (name "/SPI3_MISO") (class "Default")
      (node (ref "X4") (pin "54") (pinfunction "54_54") (pintype "passive"))
    )
    (net (code "103") (name "/SPI3_MOSI") (class "Default")
      (node (ref "X4") (pin "53") (pinfunction "53_53") (pintype "passive"))
    )
    (net (code "104") (name "/SPI3_SCK") (class "Default")
      (node (ref "X4") (pin "52") (pinfunction "52_52") (pintype "passive"))
    )
    (net (code "105") (name "/SPI8_MISO") (class "Default")
      (node (ref "U11") (pin "12") (pinfunction "SDO_12") (pintype "passive"))
      (node (ref "U9") (pin "12") (pinfunction "SDO_12") (pintype "passive"))
      (node (ref "X4") (pin "47") (pinfunction "47_47") (pintype "passive"))
    )
    (net (code "106") (name "/SPI8_MOSI") (class "Default")
      (node (ref "U11") (pin "14") (pinfunction "SDI_14") (pintype "passive"))
      (node (ref "U9") (pin "14") (pinfunction "SDI_14") (pintype "passive"))
      (node (ref "X4") (pin "48") (pinfunction "48_48") (pintype "passive"))
    )
    (net (code "107") (name "/SPI8_SCK") (class "Default")
      (node (ref "U11") (pin "13") (pinfunction "SCLK_13") (pintype "passive"))
      (node (ref "U9") (pin "13") (pinfunction "SCLK_13") (pintype "passive"))
      (node (ref "X4") (pin "46") (pinfunction "46_46") (pintype "passive"))
    )
    (net (code "108") (name "/SPI9_MOSI") (class "Default")
      (node (ref "X4") (pin "50") (pinfunction "50_50") (pintype "passive"))
    )
    (net (code "109") (name "/SPI9_SCK") (class "Default")
      (node (ref "X4") (pin "49") (pinfunction "49_49") (pintype "passive"))
    )
    (net (code "110") (name "/TXD7") (class "Default")
      (node (ref "X2") (pin "3") (pinfunction "3_3") (pintype "passive"))
    )
    (net (code "111") (name "/USBHS_N") (class "Default")
      (node (ref "X3") (pin "A7") (pinfunction "Dn1_A7") (pintype "passive"))
      (node (ref "X3") (pin "B7") (pinfunction "Dn2_B7") (pintype "passive"))
    )
    (net (code "112") (name "/USBHS_P") (class "Default")
      (node (ref "X3") (pin "A6") (pinfunction "Dp1_A6") (pintype "passive"))
      (node (ref "X3") (pin "B6") (pinfunction "Dp2_B6") (pintype "passive"))
    )
    (net (code "113") (name "/USB_N") (class "Default")
      (node (ref "X4") (pin "58") (pinfunction "58_58") (pintype "passive"))
    )
    (net (code "114") (name "/USB_P") (class "Default")
      (node (ref "X4") (pin "59") (pinfunction "59_59") (pintype "passive"))
    )
    (net (code "115") (name "GND") (class "Default")
      (node (ref "C102") (pin "2") (pinfunction "2_2") (pintype "passive"))
      (node (ref "C106") (pin "2") (pinfunction "2_2") (pintype "passive"))
      (node (ref "C52") (pin "2") (pinfunction "2_2") (pintype "passive"))
      (node (ref "C57") (pin "2") (pinfunction "2_2") (pintype "passive"))
      (node (ref "C67") (pin "2") (pinfunction "2_2") (pintype "passive"))
      (node (ref "C68") (pin "2") (pinfunction "2_2") (pintype "passive"))
      (node (ref "C71") (pin "2") (pinfunction "2_2") (pintype "passive"))
      (node (ref "C72") (pin "2") (pinfunction "2_2") (pintype "passive"))
      (node (ref "C79") (pin "2") (pinfunction "2_2") (pintype "passive"))
      (node (ref "C82") (pin "1") (pinfunction "1_1") (pintype "passive"))
      (node (ref "C83") (pin "2") (pinfunction "2_2") (pintype "passive"))
      (node (ref "C84") (pin "1") (pinfunction "1_1") (pintype "passive"))
      (node (ref "C88") (pin "2") (pinfunction "2_2") (pintype "passive"))
      (node (ref "C93") (pin "2") (pinfunction "2_2") (pintype "passive"))
      (node (ref "R41") (pin "1") (pinfunction "1_1") (pintype "passive"))
      (node (ref "R42") (pin "1") (pinfunction "1_1") (pintype "passive"))
      (node (ref "U11") (pin "17") (pinfunction "TP_17") (pintype "passive"))
      (node (ref "U11") (pin "9") (pinfunction "GND_9") (pintype "passive"))
      (node (ref "U15") (pin "2") (pinfunction "SDx_2") (pintype "passive"))
      (node (ref "U15") (pin "3") (pinfunction "SCx_3") (pintype "passive"))
      (node (ref "U15") (pin "6") (pinfunction "GND_6") (pintype "passive"))
      (node (ref "U15") (pin "7") (pinfunction "GND_7") (pintype "passive"))
      (node (ref "U18") (pin "2") (pinfunction "GND_2") (pintype "power_in"))
      (node (ref "U18") (pin "5") (pinfunction "EP_5") (pintype "power_in"))
      (node (ref "U8") (pin "2") (pinfunction "GND_2") (pintype "power_in"))
      (node (ref "U8") (pin "5") (pinfunction "EP_5") (pintype "power_in"))
      (node (ref "U9") (pin "17") (pinfunction "TP_17") (pintype "passive"))
      (node (ref "U9") (pin "9") (pinfunction "GND_9") (pintype "passive"))
      (node (ref "X2") (pin "1") (pinfunction "1_1") (pintype "passive"))
      (node (ref "X2") (pin "17") (pinfunction "17_17") (pintype "passive"))
      (node (ref "X2") (pin "18") (pinfunction "18_18") (pintype "passive"))
      (node (ref "X2") (pin "19") (pinfunction "19_19") (pintype "passive"))
      (node (ref "X2") (pin "20") (pinfunction "20_20") (pintype "passive"))
      (node (ref "X2") (pin "50") (pinfunction "50_50") (pintype "passive"))
      (node (ref "X2") (pin "53") (pinfunction "53_53") (pintype "passive"))
      (node (ref "X2") (pin "57") (pinfunction "57_57") (pintype "passive"))
      (node (ref "X2") (pin "60") (pinfunction "60_60") (pintype "passive"))
      (node (ref "X3") (pin "A1") (pinfunction "GND_A1") (pintype "passive"))
      (node (ref "X3") (pin "A12") (pinfunction "GND_A12") (pintype "passive"))
      (node (ref "X3") (pin "B1") (pinfunction "GND_B1") (pintype "passive"))
      (node (ref "X3") (pin "B12") (pinfunction "GND_B12") (pintype "passive"))
      (node (ref "X3") (pin "Shell") (pinfunction "Shield_Shell") (pintype "passive"))
      (node (ref "X4") (pin "1") (pinfunction "1_1") (pintype "passive"))
      (node (ref "X4") (pin "13") (pinfunction "13_13") (pintype "passive"))
      (node (ref "X4") (pin "30") (pinfunction "30_30") (pintype "passive"))
      (node (ref "X4") (pin "33") (pinfunction "33_33") (pintype "passive"))
      (node (ref "X4") (pin "42") (pinfunction "42_42") (pintype "passive"))
      (node (ref "X4") (pin "45") (pinfunction "45_45") (pintype "passive"))
      (node (ref "X4") (pin "51") (pinfunction "51_51") (pintype "passive"))
      (node (ref "X4") (pin "60") (pinfunction "60_60") (pintype "passive"))
      (node (ref "X6") (pin "1") (pinfunction "1_1") (pintype "passive"))
      (node (ref "X6") (pin "10") (pinfunction "6_10") (pintype "passive"))
      (node (ref "X6") (pin "14") (pinfunction "8_14") (pintype "passive"))
      (node (ref "X6") (pin "16") (pinfunction "9_16") (pintype "passive"))
      (node (ref "X6") (pin "18") (pinfunction "10_18") (pintype "passive"))
      (node (ref "X6") (pin "2") (pinfunction "2_2") (pintype "passive"))
      (node (ref "X6") (pin "9") (pinfunction "5_9") (pintype "passive"))
      (node (ref "uSD1") (pin "10") (pinfunction "WP_10") (pintype "passive"))
      (node (ref "uSD1") (pin "11") (pinfunction "GND_11") (pintype "passive"))
      (node (ref "uSD1") (pin "12") (pinfunction "GND_12") (pintype "passive"))
      (node (ref "uSD1") (pin "6") (pinfunction "VSS2_6") (pintype "passive"))
      (node (ref "uSD1") (pin "9") (pintype "passive"))
    )
    (net (code "116") (name "Net-(U9-DECAP)") (class "Default")
      (node (ref "C67") (pin "1") (pinfunction "1_1") (pintype "passive"))
      (node (ref "U9") (pin "8") (pinfunction "DECAP_8") (pintype "passive"))
    )
    (net (code "117") (name "Net-(U11-DECAP)") (class "Default")
      (node (ref "C83") (pin "1") (pinfunction "1_1") (pintype "passive"))
      (node (ref "U11") (pin "8") (pinfunction "DECAP_8") (pintype "passive"))
    )
    (net (code "118") (name "Net-(U15-CS)") (class "Default")
      (node (ref "R43") (pin "2") (pinfunction "2_2") (pintype "passive"))
      (node (ref "U15") (pin "12") (pinfunction "CS_12") (pintype "passive"))
    )
    (net (code "119") (name "Net-(U15-SDO)") (class "Default")
      (node (ref "R44") (pin "1") (pinfunction "1_1") (pintype "passive"))
      (node (ref "U15") (pin "1") (pinfunction "SDO_1") (pintype "passive"))
    )
    (net (code "120") (name "Net-(X3-CC)") (class "Default")
      (node (ref "R42") (pin "2") (pinfunction "2_2") (pintype "passive"))
      (node (ref "X3") (pin "A5") (pinfunction "CC_A5") (pintype "passive"))
    )
    (net (code "121") (name "Net-(X3-VCONN)") (class "Default")
      (node (ref "R41") (pin "2") (pinfunction "2_2") (pintype "passive"))
      (node (ref "X3") (pin "B5") (pinfunction "VCONN_B5") (pintype "passive"))
    )
    (net (code "122") (name "unconnected-(U15-INT1-Pad4)") (class "Default")
      (node (ref "U15") (pin "4") (pinfunction "INT1_4") (pintype "passive"))
    )
    (net (code "123") (name "unconnected-(U15-OCSA-Pad10)") (class "Default")
      (node (ref "U15") (pin "10") (pinfunction "OCSA_10") (pintype "passive"))
    )
    (net (code "124") (name "unconnected-(U15-SDOA-Pad11)") (class "Default")
      (node (ref "U15") (pin "11") (pinfunction "SDOA_11") (pintype "passive"))
    )
    (net (code "125") (name "unconnected-(X2-Pad14)") (class "Default")
      (node (ref "X2") (pin "14") (pinfunction "14_14") (pintype "passive"))
    )
    (net (code "126") (name "unconnected-(X2-Pad15)") (class "Default")
      (node (ref "X2") (pin "15") (pinfunction "15_15") (pintype "passive"))
    )
    (net (code "127") (name "unconnected-(X2-Pad16)") (class "Default")
      (node (ref "X2") (pin "16") (pinfunction "16_16") (pintype "passive"))
    )
    (net (code "128") (name "unconnected-(X3-SBU1-PadA8)") (class "Default")
      (node (ref "X3") (pin "A8") (pinfunction "SBU1_A8") (pintype "passive"))
    )
    (net (code "129") (name "unconnected-(X3-SBU2-PadB8)") (class "Default")
      (node (ref "X3") (pin "B8") (pinfunction "SBU2_B8") (pintype "passive"))
    )
    (net (code "130") (name "unconnected-(X3-SSRXn1-PadB10)") (class "Default")
      (node (ref "X3") (pin "B10") (pinfunction "SSRXn1_B10") (pintype "passive"))
    )
    (net (code "131") (name "unconnected-(X3-SSRXn2-PadA10)") (class "Default")
      (node (ref "X3") (pin "A10") (pinfunction "SSRXn2_A10") (pintype "passive"))
    )
    (net (code "132") (name "unconnected-(X3-SSRXp1-PadB11)") (class "Default")
      (node (ref "X3") (pin "B11") (pinfunction "SSRXp1_B11") (pintype "passive"))
    )
    (net (code "133") (name "unconnected-(X3-SSRXp2-PadA11)") (class "Default")
      (node (ref "X3") (pin "A11") (pinfunction "SSRXp2_A11") (pintype "passive"))
    )
    (net (code "134") (name "unconnected-(X3-SSTXn1-PadA3)") (class "Default")
      (node (ref "X3") (pin "A3") (pinfunction "SSTXn1_A3") (pintype "passive"))
    )
    (net (code "135") (name "unconnected-(X3-SSTXn2-PadB3)") (class "Default")
      (node (ref "X3") (pin "B3") (pinfunction "SSTXn2_B3") (pintype "passive"))
    )
    (net (code "136") (name "unconnected-(X3-SSTXp1-PadA2)") (class "Default")
      (node (ref "X3") (pin "A2") (pinfunction "SSTXp1_A2") (pintype "passive"))
    )
    (net (code "137") (name "unconnected-(X3-SSTXp2-PadB2)") (class "Default")
      (node (ref "X3") (pin "B2") (pinfunction "SSTXp2_B2") (pintype "passive"))
    )
    (net (code "138") (name "unconnected-(X6-2-Pad3)") (class "Default")
      (node (ref "X6") (pin "3") (pinfunction "2_3") (pintype "passive"))
    )
    (net (code "139") (name "unconnected-(X6-3-Pad4)") (class "Default")
      (node (ref "X6") (pin "4") (pinfunction "3_4") (pintype "passive"))
    )
    (net (code "140") (name "unconnected-(X6-3-Pad5)") (class "Default")
      (node (ref "X6") (pin "5") (pinfunction "3_5") (pintype "passive"))
    )
    (net (code "141") (name "unconnected-(X6-4-Pad6)") (class "Default")
      (node (ref "X6") (pin "6") (pinfunction "4_6") (pintype "passive"))
    )
    (net (code "142") (name "unconnected-(X6-4-Pad7)") (class "Default")
      (node (ref "X6") (pin "7") (pinfunction "4_7") (pintype "passive"))
    )
    (net (code "143") (name "unconnected-(X6-5-Pad8)") (class "Default")
      (node (ref "X6") (pin "8") (pinfunction "5_8") (pintype "passive"))
    )
  )
)
